# P01_POWER_USB.net
KiCad netlist of a schematic drawn in EasyEDA
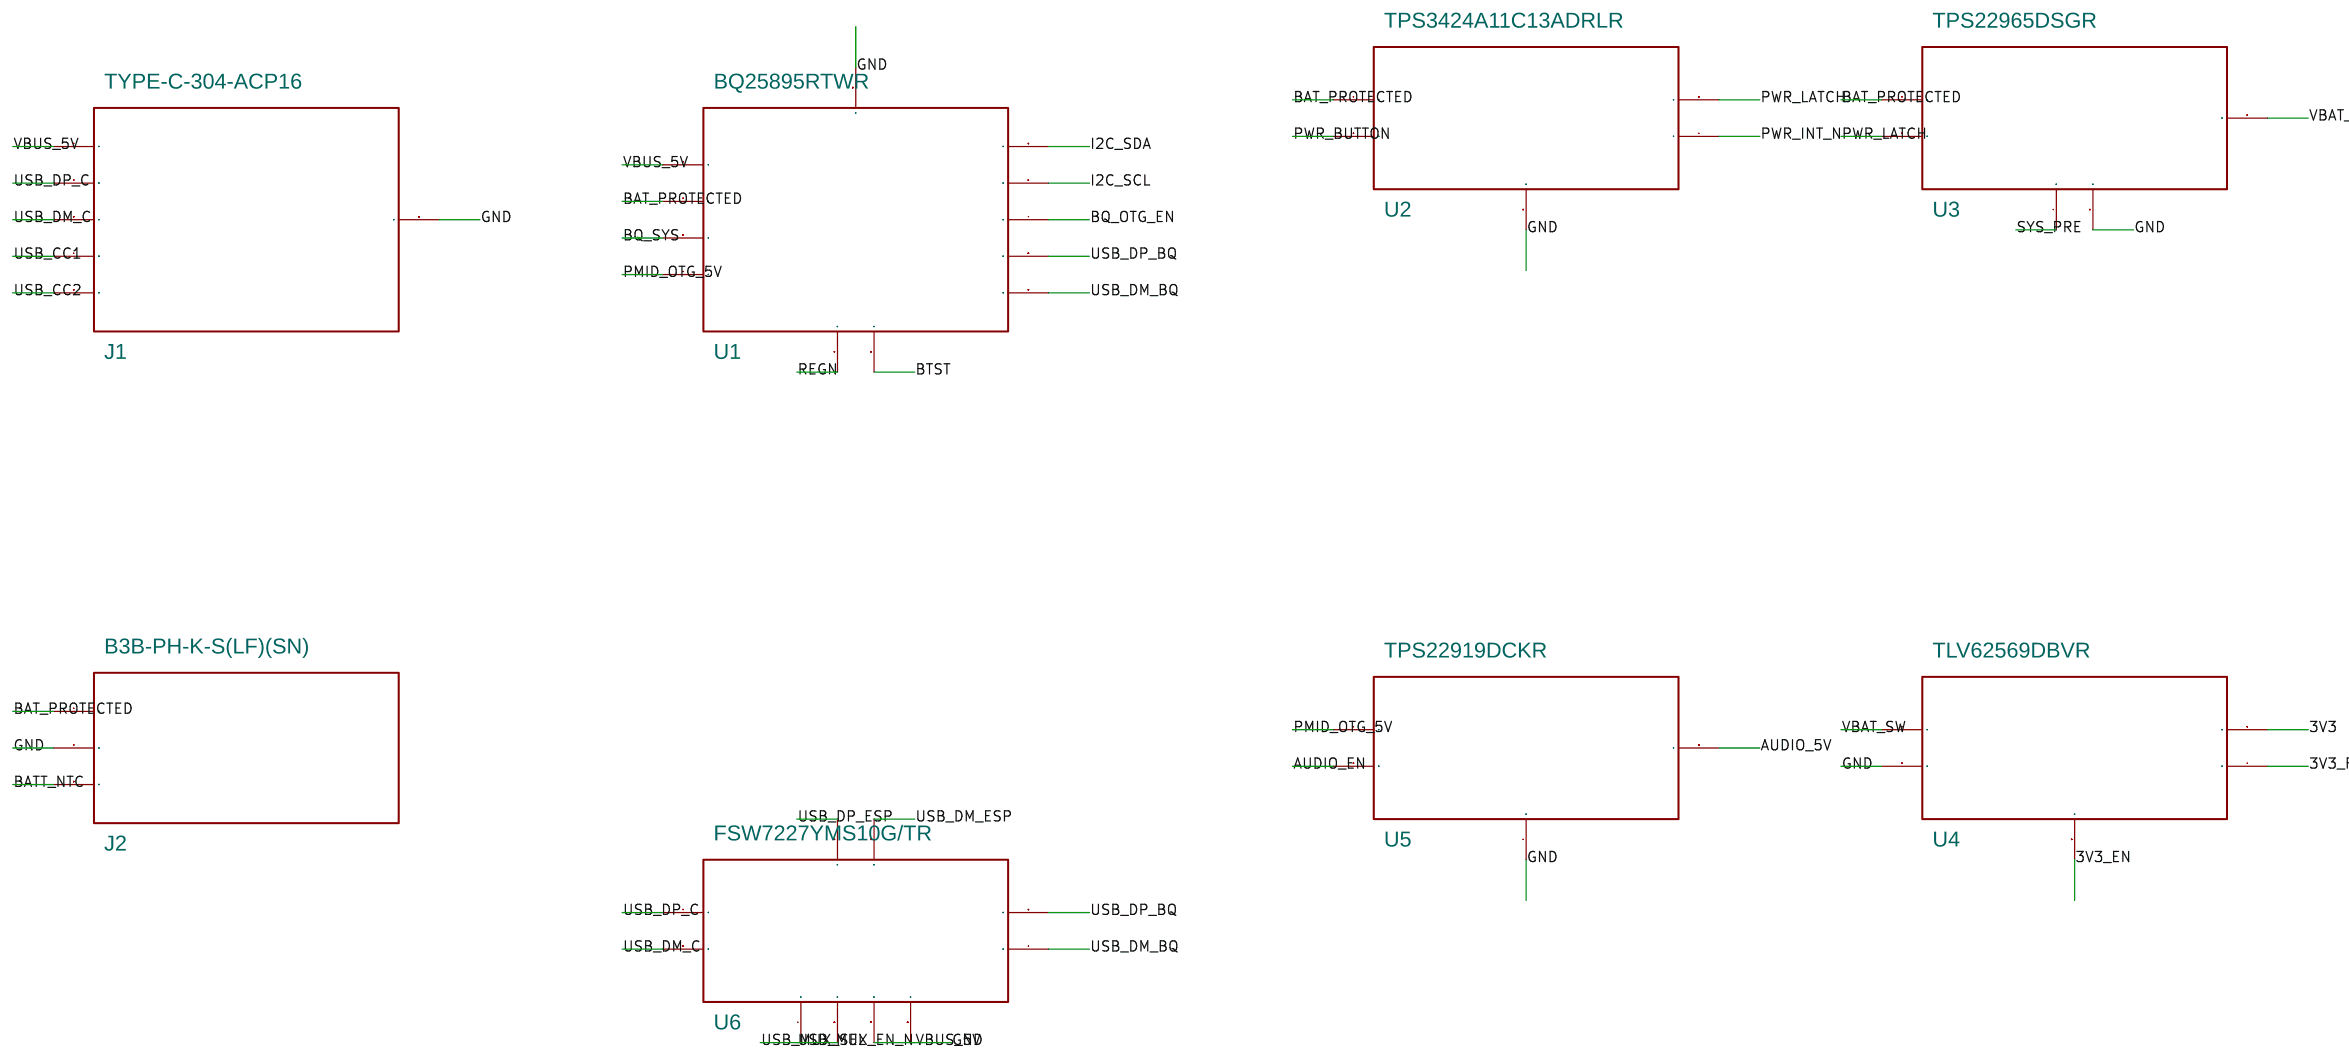
[diagram p0: schematic sheet]

(export (version "E")
  (design (tool "Eeschema 10.0.6"))
  (components
    (comp (ref "J1") (value "TYPE-C-304-ACP16") (libsource (lib "") (part "Connector")))
    (comp (ref "J2") (value "B3B-PH-K-S(LF)(SN)") (libsource (lib "") (part "Connector_1")))
    (comp (ref "U1") (value "BQ25895RTWR") (libsource (lib "") (part "BQ25895")))
    (comp (ref "U2") (value "TPS3424A11C13ADRLR") (libsource (lib "") (part "Pushbutton_Controller")))
    (comp (ref "U3") (value "TPS22965DSGR") (libsource (lib "") (part "Load_Switch")))
    (comp (ref "U4") (value "TLV62569DBVR") (libsource (lib "") (part "Buck_Regulator")))
    (comp (ref "U5") (value "TPS22919DCKR") (libsource (lib "") (part "Load_Switch_1")))
    (comp (ref "U6") (value "FSW7227YMS10G/TR") (libsource (lib "") (part "USB2_Mux")))
  )
  (nets
    (net (code "1") (name "/3V3") (class "Default")
      (node (ref "U4") (pin "3") (pinfunction "1_3") (pintype "unspecified"))
    )
    (net (code "2") (name "/3V3_EN") (class "Default")
      (node (ref "U4") (pin "5") (pinfunction "1_5") (pintype "unspecified"))
    )
    (net (code "3") (name "/3V3_FB") (class "Default")
      (node (ref "U4") (pin "4") (pinfunction "1_4") (pintype "unspecified"))
    )
    (net (code "4") (name "/AUDIO_5V") (class "Default")
      (node (ref "U5") (pin "3") (pinfunction "1_3") (pintype "unspecified"))
    )
    (net (code "5") (name "/AUDIO_EN") (class "Default")
      (node (ref "U5") (pin "2") (pinfunction "1_2") (pintype "unspecified"))
    )
    (net (code "6") (name "/BATT_NTC") (class "Default")
      (node (ref "J2") (pin "3") (pinfunction "1_3") (pintype "unspecified"))
    )
    (net (code "7") (name "/BAT_PROTECTED") (class "Default")
      (node (ref "J2") (pin "1") (pinfunction "1_1") (pintype "unspecified"))
      (node (ref "U1") (pin "2") (pinfunction "1_2") (pintype "unspecified"))
      (node (ref "U2") (pin "1") (pinfunction "1_1") (pintype "unspecified"))
      (node (ref "U3") (pin "1") (pinfunction "1_1") (pintype "unspecified"))
    )
    (net (code "8") (name "/BQ_OTG_EN") (class "Default")
      (node (ref "U1") (pin "7") (pinfunction "1_7") (pintype "unspecified"))
    )
    (net (code "9") (name "/BQ_SYS") (class "Default")
      (node (ref "U1") (pin "3") (pinfunction "1_3") (pintype "unspecified"))
    )
    (net (code "10") (name "/BTST") (class "Default")
      (node (ref "U1") (pin "12") (pinfunction "1_12") (pintype "unspecified"))
    )
    (net (code "11") (name "/GND") (class "Default")
      (node (ref "J1") (pin "1") (pinfunction "1_1") (pintype "unspecified"))
      (node (ref "J1") (pin "6") (pinfunction "1_6") (pintype "unspecified"))
      (node (ref "J2") (pin "2") (pinfunction "1_2") (pintype "unspecified"))
      (node (ref "U1") (pin "1") (pinfunction "1_1") (pintype "unspecified"))
      (node (ref "U1") (pin "10") (pinfunction "1_10") (pintype "unspecified"))
      (node (ref "U2") (pin "5") (pinfunction "1_5") (pintype "unspecified"))
      (node (ref "U3") (pin "5") (pinfunction "1_5") (pintype "unspecified"))
      (node (ref "U4") (pin "2") (pinfunction "1_2") (pintype "unspecified"))
      (node (ref "U5") (pin "4") (pinfunction "1_4") (pintype "unspecified"))
      (node (ref "U6") (pin "10") (pinfunction "1_10") (pintype "unspecified"))
      (node (ref "U6") (pin "9") (pinfunction "1_9") (pintype "unspecified"))
    )
    (net (code "12") (name "/I2C_SCL") (class "Default")
      (node (ref "U1") (pin "6") (pinfunction "1_6") (pintype "unspecified"))
    )
    (net (code "13") (name "/I2C_SDA") (class "Default")
      (node (ref "U1") (pin "5") (pinfunction "1_5") (pintype "unspecified"))
    )
    (net (code "14") (name "/PMID_OTG_5V") (class "Default")
      (node (ref "U1") (pin "4") (pinfunction "1_4") (pintype "unspecified"))
      (node (ref "U5") (pin "1") (pinfunction "1_1") (pintype "unspecified"))
    )
    (net (code "15") (name "/PWR_BUTTON") (class "Default")
      (node (ref "U2") (pin "2") (pinfunction "1_2") (pintype "unspecified"))
    )
    (net (code "16") (name "/PWR_INT_N") (class "Default")
      (node (ref "U2") (pin "4") (pinfunction "1_4") (pintype "unspecified"))
    )
    (net (code "17") (name "/PWR_LATCH") (class "Default")
      (node (ref "U2") (pin "3") (pinfunction "1_3") (pintype "unspecified"))
      (node (ref "U3") (pin "2") (pinfunction "1_2") (pintype "unspecified"))
    )
    (net (code "18") (name "/REGN") (class "Default")
      (node (ref "U1") (pin "11") (pinfunction "1_11") (pintype "unspecified"))
    )
    (net (code "19") (name "/SYS_PRE") (class "Default")
      (node (ref "U3") (pin "4") (pinfunction "1_4") (pintype "unspecified"))
    )
    (net (code "20") (name "/USB_CC1") (class "Default")
      (node (ref "J1") (pin "4") (pinfunction "1_4") (pintype "unspecified"))
    )
    (net (code "21") (name "/USB_CC2") (class "Default")
      (node (ref "J1") (pin "5") (pinfunction "1_5") (pintype "unspecified"))
    )
    (net (code "22") (name "/USB_DM_BQ") (class "Default")
      (node (ref "U1") (pin "9") (pinfunction "1_9") (pintype "unspecified"))
      (node (ref "U6") (pin "4") (pinfunction "1_4") (pintype "unspecified"))
    )
    (net (code "23") (name "/USB_DM_C") (class "Default")
      (node (ref "J1") (pin "3") (pinfunction "1_3") (pintype "unspecified"))
      (node (ref "U6") (pin "2") (pinfunction "1_2") (pintype "unspecified"))
    )
    (net (code "24") (name "/USB_DM_ESP") (class "Default")
      (node (ref "U6") (pin "6") (pinfunction "1_6") (pintype "unspecified"))
    )
    (net (code "25") (name "/USB_DP_BQ") (class "Default")
      (node (ref "U1") (pin "8") (pinfunction "1_8") (pintype "unspecified"))
      (node (ref "U6") (pin "3") (pinfunction "1_3") (pintype "unspecified"))
    )
    (net (code "26") (name "/USB_DP_C") (class "Default")
      (node (ref "J1") (pin "2") (pinfunction "1_2") (pintype "unspecified"))
      (node (ref "U6") (pin "1") (pinfunction "1_1") (pintype "unspecified"))
    )
    (net (code "27") (name "/USB_DP_ESP") (class "Default")
      (node (ref "U6") (pin "5") (pinfunction "1_5") (pintype "unspecified"))
    )
    (net (code "28") (name "/USB_MUX_EN_N") (class "Default")
      (node (ref "U6") (pin "7") (pinfunction "1_7") (pintype "unspecified"))
      (node (ref "U6") (pin "8") (pinfunction "1_8") (pintype "unspecified"))
    )
    (net (code "29") (name "/VBAT_SW") (class "Default")
      (node (ref "U3") (pin "3") (pinfunction "1_3") (pintype "unspecified"))
      (node (ref "U4") (pin "1") (pinfunction "1_1") (pintype "unspecified"))
    )
  )
)
